# d7hb.net
KiCad netlist of a schematic drawn in EAGLE
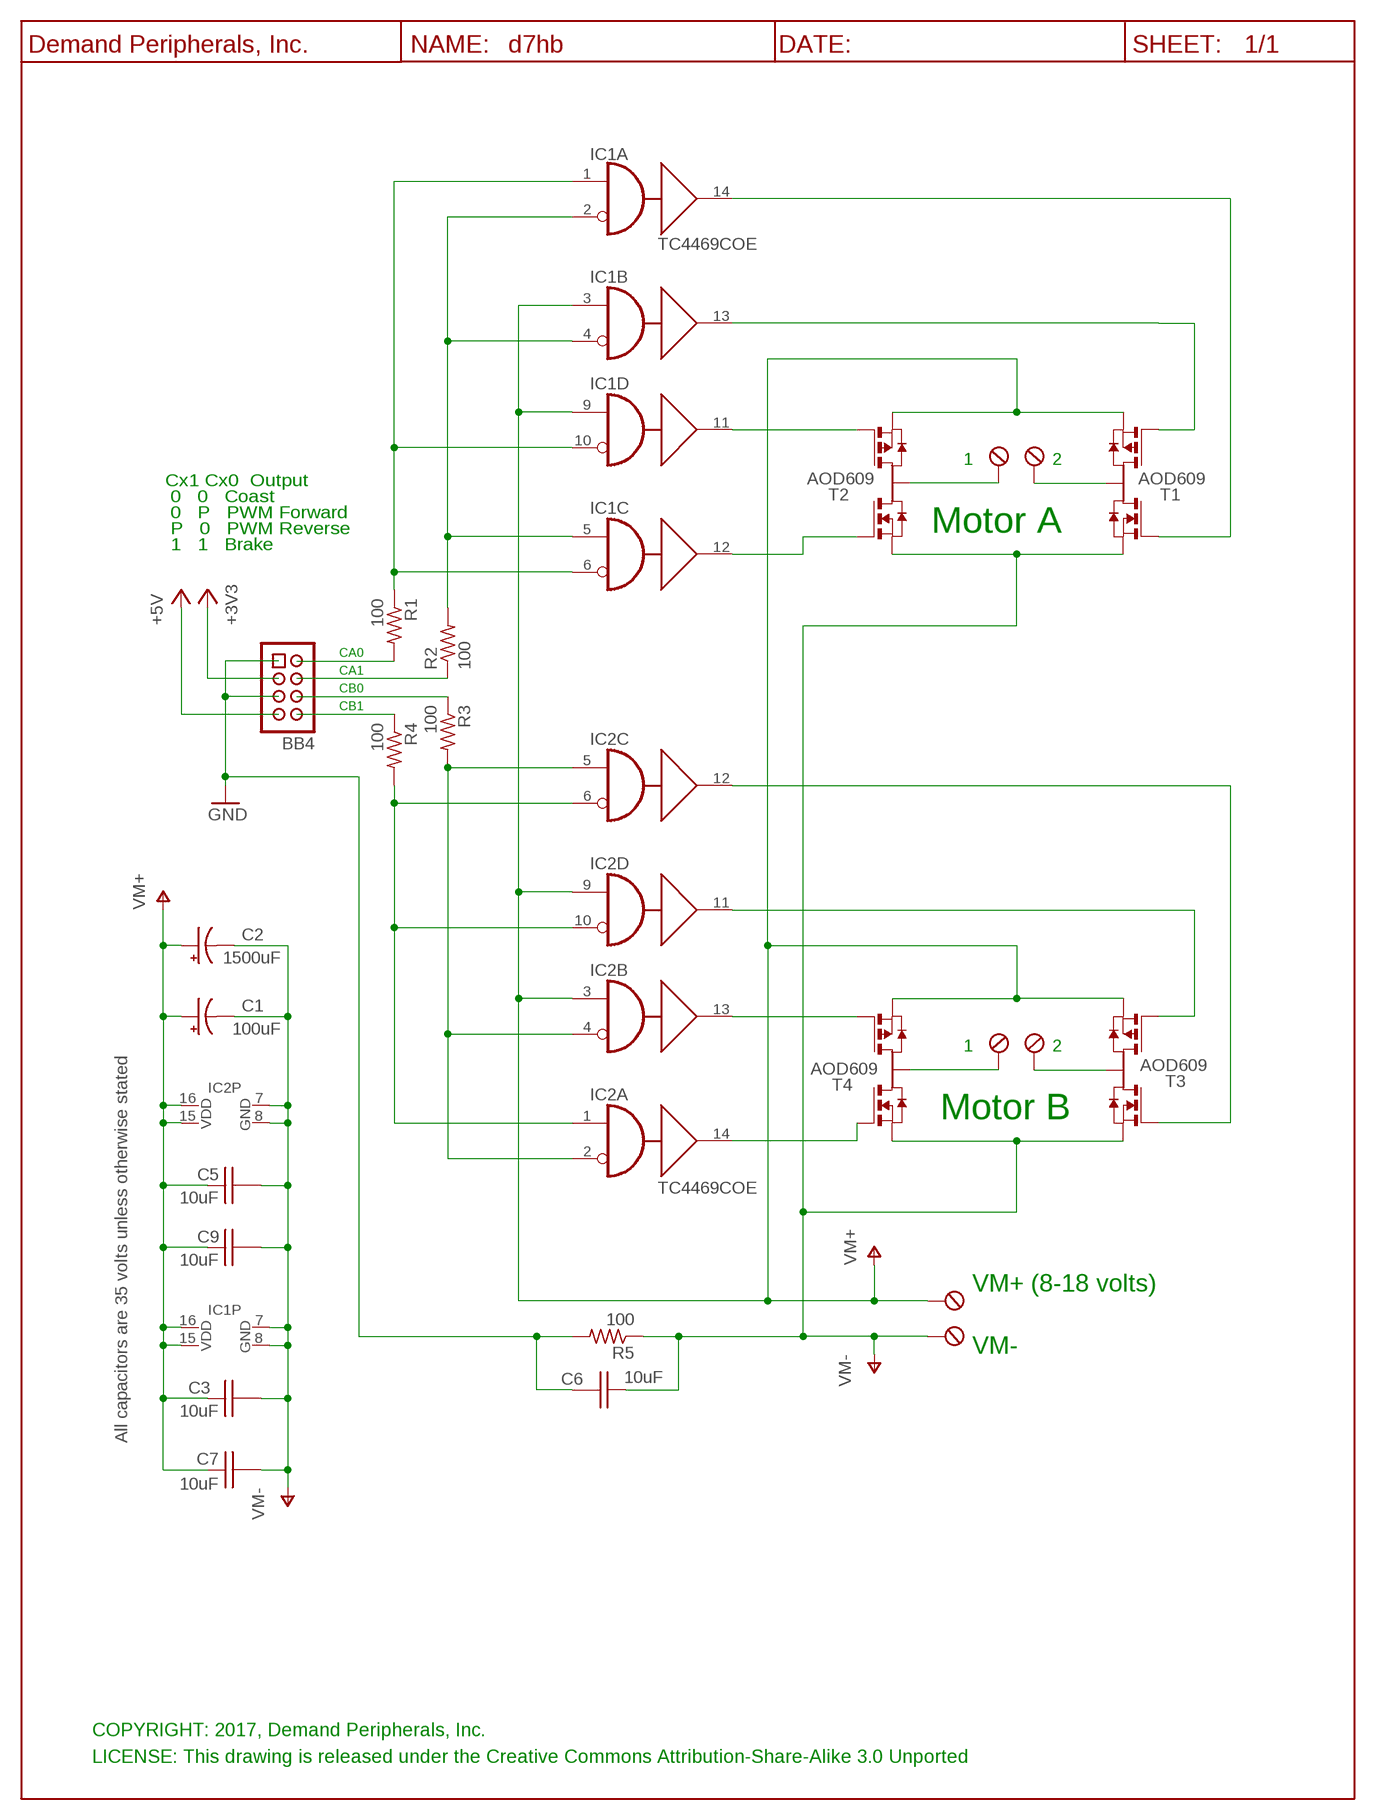
[diagram p0: schematic, sheet 1]

(export (version "E")
  (design (tool "Eeschema 10.0.6"))
  (components
    (comp (ref "BB4")
      (value "BB_CON")
      (footprint "eagle-import:HDR-4X2")
      (libsource (lib "eagle-import") (part "HDR-4X2-SHR"))
    )
    (comp (ref "C1")
      (value "100uF")
      (footprint "eagle-import:E3.5-8")
      (libsource (lib "eagle-import") (part "C100UF35V_E3.5-8"))
    )
    (comp (ref "C2")
      (value "1500uF")
      (footprint "eagle-import:E7,5-16")
      (libsource (lib "eagle-import") (part "C1500UF35V_E7,5-16"))
    )
    (comp (ref "C3")
      (value "10uF")
      (footprint "eagle-import:C0805")
      (libsource (lib "eagle-import") (part "C10UF35V_C0805"))
    )
    (comp (ref "C5")
      (value "10uF")
      (footprint "eagle-import:C0805")
      (libsource (lib "eagle-import") (part "C10UF35V_C0805"))
    )
    (comp (ref "C6")
      (value "10uF")
      (footprint "eagle-import:C0805")
      (libsource (lib "eagle-import") (part "C10UF35V_C0805"))
    )
    (comp (ref "C7")
      (value "10uF")
      (footprint "eagle-import:C0805")
      (libsource (lib "eagle-import") (part "C10UF35V_C0805"))
    )
    (comp (ref "C9")
      (value "10uF")
      (footprint "eagle-import:C0805")
      (libsource (lib "eagle-import") (part "C10UF35V_C0805"))
    )
    (comp (ref "CN1")
      (value "OSTTC022162")
      (footprint "eagle-import:TBLK-5.08-X2")
      (libsource (lib "eagle-import") (part "TBLK-5.08-X2"))
    )
    (comp (ref "CN2")
      (value "OSTTC022162")
      (footprint "eagle-import:TBLK-5.08-X2")
      (libsource (lib "eagle-import") (part "TBLK-5.08-X2"))
    )
    (comp (ref "CN3")
      (value "OSTTC022162")
      (footprint "eagle-import:TBLK-5.08-X2")
      (libsource (lib "eagle-import") (part "TBLK-5.08-X2"))
    )
    (comp (ref "IC1")
      (value "TC4469COE")
      (footprint "eagle-import:SO-16DW")
      (libsource (lib "eagle-import") (part "TC4469OESO-16DW"))
    )
    (comp (ref "IC2")
      (value "TC4469COE")
      (footprint "eagle-import:SO-16DW")
      (libsource (lib "eagle-import") (part "TC4469OESO-16DW"))
    )
    (comp (ref "R1")
      (value "100")
      (footprint "eagle-import:R0603")
      (libsource (lib "eagle-import") (part "R100_R0603"))
    )
    (comp (ref "R2")
      (value "100")
      (footprint "eagle-import:R0603")
      (libsource (lib "eagle-import") (part "R100_R0603"))
    )
    (comp (ref "R3")
      (value "100")
      (footprint "eagle-import:R0603")
      (libsource (lib "eagle-import") (part "R100_R0603"))
    )
    (comp (ref "R4")
      (value "100")
      (footprint "eagle-import:R0603")
      (libsource (lib "eagle-import") (part "R100_R0603"))
    )
    (comp (ref "R5")
      (value "100")
      (footprint "eagle-import:R0603")
      (libsource (lib "eagle-import") (part "R100_R0603"))
    )
    (comp (ref "T1")
      (value "AOD609")
      (footprint "eagle-import:TO252-41")
      (libsource (lib "eagle-import") (part "AOD609"))
    )
    (comp (ref "T2")
      (value "AOD609")
      (footprint "eagle-import:TO252-41")
      (libsource (lib "eagle-import") (part "AOD609"))
    )
    (comp (ref "T3")
      (value "AOD609")
      (footprint "eagle-import:TO252-41")
      (libsource (lib "eagle-import") (part "AOD609"))
    )
    (comp (ref "T4")
      (value "AOD609")
      (footprint "eagle-import:TO252-41")
      (libsource (lib "eagle-import") (part "AOD609"))
    )
    (comp (ref "U$1")
      (value "DP_FRAME_P")
      (footprint "eagle-import:LETTER_P")
      (libsource (lib "eagle-import") (part "DP_FRAME_P"))
    )
  )
  (nets
    (net (code "1") (name "+3V3") (class "Default")
      (node (ref "BB4") (pin "3") (pinfunction "3_3") (pintype "passive"))
    )
    (net (code "2") (name "+5V") (class "Default")
      (node (ref "BB4") (pin "7") (pinfunction "7_7") (pintype "passive"))
    )
    (net (code "3") (name "GND") (class "Default")
      (node (ref "BB4") (pin "1") (pinfunction "1_1") (pintype "passive"))
      (node (ref "BB4") (pin "5") (pinfunction "5_5") (pintype "passive"))
      (node (ref "C6") (pin "2") (pinfunction "2_2") (pintype "passive"))
      (node (ref "R5") (pin "2") (pinfunction "2_2") (pintype "passive"))
    )
    (net (code "4") (name "Net-(BB4-Pad2)") (class "Default")
      (node (ref "BB4") (pin "2") (pinfunction "2_2") (pintype "passive"))
      (node (ref "R1") (pin "2") (pinfunction "2_2") (pintype "passive"))
    )
    (net (code "5") (name "Net-(BB4-Pad4)") (class "Default")
      (node (ref "BB4") (pin "4") (pinfunction "4_4") (pintype "passive"))
      (node (ref "R2") (pin "1") (pinfunction "1_1") (pintype "passive"))
    )
    (net (code "6") (name "Net-(BB4-Pad6)") (class "Default")
      (node (ref "BB4") (pin "6") (pinfunction "6_6") (pintype "passive"))
      (node (ref "R3") (pin "1") (pinfunction "1_1") (pintype "passive"))
    )
    (net (code "7") (name "Net-(BB4-Pad8)") (class "Default")
      (node (ref "BB4") (pin "8") (pinfunction "8_8") (pintype "passive"))
      (node (ref "R4") (pin "1") (pinfunction "1_1") (pintype "passive"))
    )
    (net (code "8") (name "Net-(CN2-KL)") (class "Default")
      (node (ref "CN2") (pin "1") (pinfunction "KL_1") (pintype "passive"))
      (node (ref "T3") (pin "CASE") (pinfunction "D12_CASE") (pintype "passive"))
    )
    (net (code "9") (name "Net-(CN2-KL1)") (class "Default")
      (node (ref "CN2") (pin "2") (pinfunction "KL1_2") (pintype "passive"))
      (node (ref "T4") (pin "CASE") (pinfunction "D12_CASE") (pintype "passive"))
    )
    (net (code "10") (name "Net-(CN3-KL)") (class "Default")
      (node (ref "CN3") (pin "1") (pinfunction "KL_1") (pintype "passive"))
      (node (ref "T2") (pin "CASE") (pinfunction "D12_CASE") (pintype "passive"))
    )
    (net (code "11") (name "Net-(CN3-KL1)") (class "Default")
      (node (ref "CN3") (pin "2") (pinfunction "KL1_2") (pintype "passive"))
      (node (ref "T1") (pin "CASE") (pinfunction "D12_CASE") (pintype "passive"))
    )
    (net (code "12") (name "Net-(IC1A-A)") (class "Default")
      (node (ref "IC1") (pin "1") (pinfunction "A_1") (pintype "input"))
      (node (ref "IC1") (pin "10") (pinfunction "B_10") (pintype "input"))
      (node (ref "IC1") (pin "6") (pinfunction "B_6") (pintype "input"))
      (node (ref "R1") (pin "1") (pinfunction "1_1") (pintype "passive"))
    )
    (net (code "13") (name "Net-(IC1A-B)") (class "Default")
      (node (ref "IC1") (pin "2") (pinfunction "B_2") (pintype "input"))
      (node (ref "IC1") (pin "4") (pinfunction "B_4") (pintype "input"))
      (node (ref "IC1") (pin "5") (pinfunction "A_5") (pintype "input"))
      (node (ref "R2") (pin "2") (pinfunction "2_2") (pintype "passive"))
    )
    (net (code "14") (name "Net-(IC1A-Y)") (class "Default")
      (node (ref "IC1") (pin "14") (pinfunction "Y_14") (pintype "output"))
      (node (ref "T1") (pin "2") (pinfunction "G1N_2") (pintype "passive"))
    )
    (net (code "15") (name "Net-(IC1B-Y)") (class "Default")
      (node (ref "IC1") (pin "13") (pinfunction "Y_13") (pintype "output"))
      (node (ref "T1") (pin "5") (pinfunction "G2P_5") (pintype "passive"))
    )
    (net (code "16") (name "Net-(IC1C-Y)") (class "Default")
      (node (ref "IC1") (pin "12") (pinfunction "Y_12") (pintype "output"))
      (node (ref "T2") (pin "2") (pinfunction "G1N_2") (pintype "passive"))
    )
    (net (code "17") (name "Net-(IC1D-Y)") (class "Default")
      (node (ref "IC1") (pin "11") (pinfunction "Y_11") (pintype "output"))
      (node (ref "T2") (pin "5") (pinfunction "G2P_5") (pintype "passive"))
    )
    (net (code "18") (name "Net-(IC2A-A)") (class "Default")
      (node (ref "IC2") (pin "1") (pinfunction "A_1") (pintype "input"))
      (node (ref "IC2") (pin "10") (pinfunction "B_10") (pintype "input"))
      (node (ref "IC2") (pin "6") (pinfunction "B_6") (pintype "input"))
      (node (ref "R4") (pin "2") (pinfunction "2_2") (pintype "passive"))
    )
    (net (code "19") (name "Net-(IC2A-B)") (class "Default")
      (node (ref "IC2") (pin "2") (pinfunction "B_2") (pintype "input"))
      (node (ref "IC2") (pin "4") (pinfunction "B_4") (pintype "input"))
      (node (ref "IC2") (pin "5") (pinfunction "A_5") (pintype "input"))
      (node (ref "R3") (pin "2") (pinfunction "2_2") (pintype "passive"))
    )
    (net (code "20") (name "Net-(IC2A-Y)") (class "Default")
      (node (ref "IC2") (pin "14") (pinfunction "Y_14") (pintype "output"))
      (node (ref "T4") (pin "2") (pinfunction "G1N_2") (pintype "passive"))
    )
    (net (code "21") (name "Net-(IC2B-Y)") (class "Default")
      (node (ref "IC2") (pin "13") (pinfunction "Y_13") (pintype "output"))
      (node (ref "T4") (pin "5") (pinfunction "G2P_5") (pintype "passive"))
    )
    (net (code "22") (name "Net-(IC2C-Y)") (class "Default")
      (node (ref "IC2") (pin "12") (pinfunction "Y_12") (pintype "output"))
      (node (ref "T3") (pin "2") (pinfunction "G1N_2") (pintype "passive"))
    )
    (net (code "23") (name "Net-(IC2D-Y)") (class "Default")
      (node (ref "IC2") (pin "11") (pinfunction "Y_11") (pintype "output"))
      (node (ref "T3") (pin "5") (pinfunction "G2P_5") (pintype "passive"))
    )
    (net (code "24") (name "VM+") (class "Default")
      (node (ref "C1") (pin "+") (pinfunction "+_+") (pintype "passive"))
      (node (ref "C2") (pin "+") (pinfunction "+_+") (pintype "passive"))
      (node (ref "C3") (pin "1") (pinfunction "1_1") (pintype "passive"))
      (node (ref "C5") (pin "1") (pinfunction "1_1") (pintype "passive"))
      (node (ref "C7") (pin "1") (pinfunction "1_1") (pintype "passive"))
      (node (ref "C9") (pin "1") (pinfunction "1_1") (pintype "passive"))
      (node (ref "CN1") (pin "2") (pinfunction "KL1_2") (pintype "passive"))
      (node (ref "IC1") (pin "15") (pinfunction "VDD_15") (pintype "power_in"))
      (node (ref "IC1") (pin "16") (pinfunction "VDD_16") (pintype "power_in"))
      (node (ref "IC1") (pin "3") (pinfunction "A_3") (pintype "input"))
      (node (ref "IC1") (pin "9") (pinfunction "A_9") (pintype "input"))
      (node (ref "IC2") (pin "15") (pinfunction "VDD_15") (pintype "power_in"))
      (node (ref "IC2") (pin "16") (pinfunction "VDD_16") (pintype "power_in"))
      (node (ref "IC2") (pin "3") (pinfunction "A_3") (pintype "input"))
      (node (ref "IC2") (pin "9") (pinfunction "A_9") (pintype "input"))
      (node (ref "T1") (pin "4") (pinfunction "S2P_4") (pintype "passive"))
      (node (ref "T2") (pin "4") (pinfunction "S2P_4") (pintype "passive"))
      (node (ref "T3") (pin "4") (pinfunction "S2P_4") (pintype "passive"))
      (node (ref "T4") (pin "4") (pinfunction "S2P_4") (pintype "passive"))
    )
    (net (code "25") (name "VM-") (class "Default")
      (node (ref "C1") (pin "-") (pinfunction "-_-") (pintype "passive"))
      (node (ref "C2") (pin "-") (pinfunction "-_-") (pintype "passive"))
      (node (ref "C3") (pin "2") (pinfunction "2_2") (pintype "passive"))
      (node (ref "C5") (pin "2") (pinfunction "2_2") (pintype "passive"))
      (node (ref "C6") (pin "1") (pinfunction "1_1") (pintype "passive"))
      (node (ref "C7") (pin "2") (pinfunction "2_2") (pintype "passive"))
      (node (ref "C9") (pin "2") (pinfunction "2_2") (pintype "passive"))
      (node (ref "CN1") (pin "1") (pinfunction "KL_1") (pintype "passive"))
      (node (ref "IC1") (pin "7") (pinfunction "GND_7") (pintype "power_in"))
      (node (ref "IC1") (pin "8") (pinfunction "GND_8") (pintype "power_in"))
      (node (ref "IC2") (pin "7") (pinfunction "GND_7") (pintype "power_in"))
      (node (ref "IC2") (pin "8") (pinfunction "GND_8") (pintype "power_in"))
      (node (ref "R5") (pin "1") (pinfunction "1_1") (pintype "passive"))
      (node (ref "T1") (pin "1") (pinfunction "S1N_1") (pintype "passive"))
      (node (ref "T2") (pin "1") (pinfunction "S1N_1") (pintype "passive"))
      (node (ref "T3") (pin "1") (pinfunction "S1N_1") (pintype "passive"))
      (node (ref "T4") (pin "1") (pinfunction "S1N_1") (pintype "passive"))
    )
  )
)
